# valhalla_v0_3.net
KiCad netlist of a schematic drawn in EAGLE
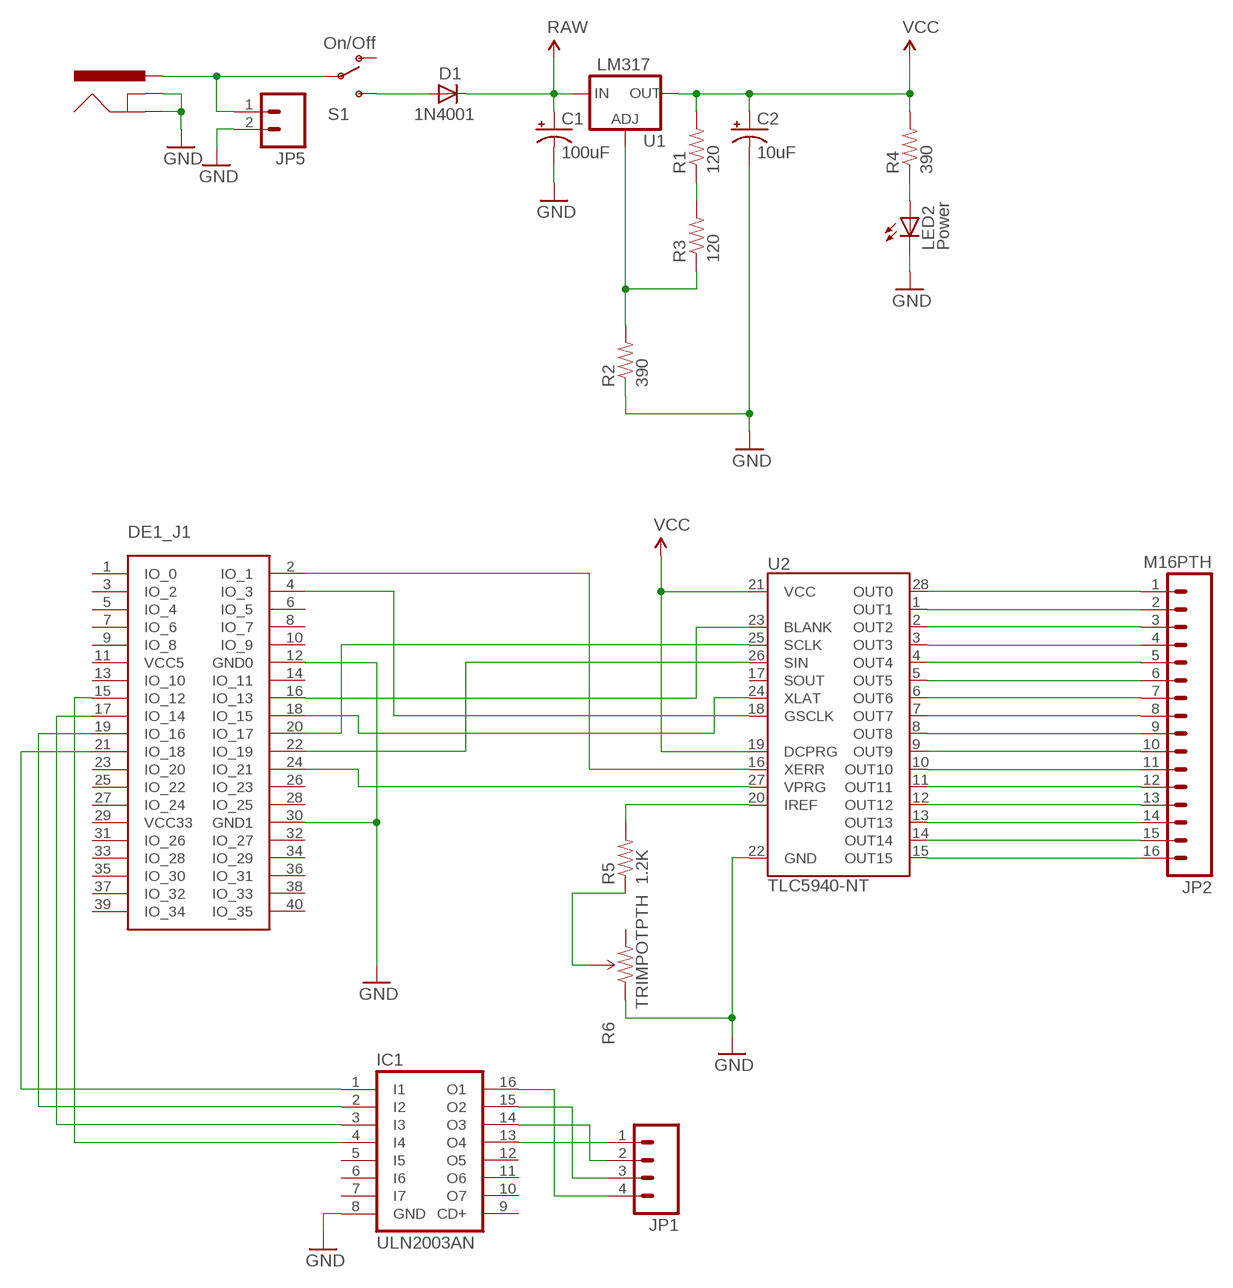
[diagram p0: schematic, sheet 1]

(export (version "E")
  (design (tool "Eeschema 10.0.6"))
  (components
    (comp (ref "C1")
      (value "100uF")
      (footprint "eagle-import:CPOL-RADIAL-100UF-25V")
      (libsource (lib "eagle-import") (part "CAP_POLPTH1"))
    )
    (comp (ref "C2")
      (value "10uF")
      (footprint "eagle-import:CPOL-RADIAL-10UF-25V")
      (libsource (lib "eagle-import") (part "CAP_POLPTH2"))
    )
    (comp (ref "D1")
      (value "1N4001")
      (footprint "eagle-import:DIODE-0.4")
      (libsource (lib "eagle-import") (part "DIODEPTH"))
    )
    (comp (ref "DE1_J1")
      (value "DE1_GPIO_CON40\"")
      (footprint "eagle-import:2X20")
      (libsource (lib "eagle-import") (part "DE1_GPIO_CON40{dblquote}"))
    )
    (comp (ref "IC1")
      (value "ULN2003AN")
      (footprint "eagle-import:DIL16")
      (libsource (lib "eagle-import") (part "ULN2003AN"))
    )
    (comp (ref "J1")
      (value "POWER_JACKPTH")
      (footprint "eagle-import:POWER_JACK_PTH")
      (libsource (lib "eagle-import") (part "POWER_JACKPTH"))
    )
    (comp (ref "JP1")
      (value "M04PTH")
      (footprint "eagle-import:1X04")
      (libsource (lib "eagle-import") (part "M04PTH"))
    )
    (comp (ref "JP2")
      (value "M16PTH")
      (footprint "eagle-import:1X16")
      (libsource (lib "eagle-import") (part "M16PTH"))
    )
    (comp (ref "JP5")
      (value "M02PTH")
      (footprint "eagle-import:1X02")
      (libsource (lib "eagle-import") (part "M02PTH"))
    )
    (comp (ref "LED2")
      (value "Power")
      (footprint "eagle-import:LED5MM")
      (libsource (lib "eagle-import") (part "LED5MM"))
    )
    (comp (ref "R1")
      (value "120")
      (footprint "eagle-import:AXIAL-0.3")
      (libsource (lib "eagle-import") (part "RESISTORPTH1"))
    )
    (comp (ref "R2")
      (value "390")
      (footprint "eagle-import:AXIAL-0.3")
      (libsource (lib "eagle-import") (part "RESISTORPTH1"))
    )
    (comp (ref "R3")
      (value "120")
      (footprint "eagle-import:AXIAL-0.3")
      (libsource (lib "eagle-import") (part "RESISTORPTH1"))
    )
    (comp (ref "R4")
      (value "390")
      (footprint "eagle-import:AXIAL-0.3")
      (libsource (lib "eagle-import") (part "RESISTORPTH1"))
    )
    (comp (ref "R5")
      (value "1.2K")
      (footprint "eagle-import:AXIAL-0.5")
      (libsource (lib "eagle-import") (part "RESISTORPTH-1/2W"))
    )
    (comp (ref "R6")
      (value "TRIMPOTPTH")
      (footprint "eagle-import:TRIM_POT_PTH")
      (libsource (lib "eagle-import") (part "TRIMPOTPTH"))
    )
    (comp (ref "S1")
      (value "On/Off")
      (footprint "eagle-import:SWITCH-SPST")
      (libsource (lib "eagle-import") (part "SWITCH-SPSTPTH"))
    )
    (comp (ref "U1")
      (value "LM317")
      (footprint "eagle-import:TO220-ADJ")
      (libsource (lib "eagle-import") (part "V_REG_317SINK"))
    )
    (comp (ref "U2")
      (value "TLC5940-NT")
      (footprint "eagle-import:DIL28-3")
      (libsource (lib "eagle-import") (part "TLC5940-NT"))
    )
  )
  (nets
    (net (code "1") (name "/VCC5") (class "Default")
      (node (ref "DE1_J1") (pin "11") (pinfunction "VCC5_11") (pintype "power_in"))
    )
    (net (code "2") (name "/VCC33") (class "Default")
      (node (ref "DE1_J1") (pin "29") (pinfunction "VCC33_29") (pintype "power_in"))
    )
    (net (code "3") (name "GND") (class "Default")
      (node (ref "C1") (pin "2") (pinfunction "-_2") (pintype "passive"))
      (node (ref "C2") (pin "2") (pinfunction "-_2") (pintype "passive"))
      (node (ref "DE1_J1") (pin "12") (pinfunction "GND0_12") (pintype "power_in"))
      (node (ref "DE1_J1") (pin "30") (pinfunction "GND1_30") (pintype "power_in"))
      (node (ref "IC1") (pin "8") (pinfunction "GND_8") (pintype "power_in"))
      (node (ref "J1") (pin "GND") (pinfunction "GND_GND") (pintype "bidirectional"))
      (node (ref "J1") (pin "GNDBREAK") (pinfunction "GNDBREAK_GNDBREAK") (pintype "bidirectional"))
      (node (ref "JP5") (pin "2") (pinfunction "2_2") (pintype "passive"))
      (node (ref "LED2") (pin "K") (pinfunction "C_K") (pintype "passive"))
      (node (ref "R2") (pin "P$1") (pinfunction "1_P$1") (pintype "passive"))
      (node (ref "R6") (pin "1") (pinfunction "CCW_1") (pintype "passive"))
      (node (ref "U2") (pin "22") (pinfunction "GND_22") (pintype "bidirectional"))
    )
    (net (code "4") (name "Net-(DE1_J1-IO_1)") (class "Default")
      (node (ref "DE1_J1") (pin "2") (pinfunction "IO_1_2") (pintype "bidirectional"))
      (node (ref "U2") (pin "16") (pinfunction "XERR_16") (pintype "bidirectional"))
    )
    (net (code "5") (name "Net-(DE1_J1-IO_3)") (class "Default")
      (node (ref "DE1_J1") (pin "4") (pinfunction "IO_3_4") (pintype "bidirectional"))
      (node (ref "U2") (pin "18") (pinfunction "GSCLK_18") (pintype "bidirectional"))
    )
    (net (code "6") (name "Net-(DE1_J1-IO_12)") (class "Default")
      (node (ref "DE1_J1") (pin "15") (pinfunction "IO_12_15") (pintype "bidirectional"))
      (node (ref "IC1") (pin "4") (pinfunction "I4_4") (pintype "input"))
    )
    (net (code "7") (name "Net-(DE1_J1-IO_13)") (class "Default")
      (node (ref "DE1_J1") (pin "16") (pinfunction "IO_13_16") (pintype "bidirectional"))
      (node (ref "U2") (pin "23") (pinfunction "BLANK_23") (pintype "bidirectional"))
    )
    (net (code "8") (name "Net-(DE1_J1-IO_14)") (class "Default")
      (node (ref "DE1_J1") (pin "17") (pinfunction "IO_14_17") (pintype "bidirectional"))
      (node (ref "IC1") (pin "3") (pinfunction "I3_3") (pintype "input"))
    )
    (net (code "9") (name "Net-(DE1_J1-IO_15)") (class "Default")
      (node (ref "DE1_J1") (pin "18") (pinfunction "IO_15_18") (pintype "bidirectional"))
      (node (ref "U2") (pin "24") (pinfunction "XLAT_24") (pintype "bidirectional"))
    )
    (net (code "10") (name "Net-(DE1_J1-IO_16)") (class "Default")
      (node (ref "DE1_J1") (pin "19") (pinfunction "IO_16_19") (pintype "bidirectional"))
      (node (ref "IC1") (pin "2") (pinfunction "I2_2") (pintype "input"))
    )
    (net (code "11") (name "Net-(DE1_J1-IO_17)") (class "Default")
      (node (ref "DE1_J1") (pin "20") (pinfunction "IO_17_20") (pintype "bidirectional"))
      (node (ref "U2") (pin "25") (pinfunction "SCLK_25") (pintype "bidirectional"))
    )
    (net (code "12") (name "Net-(DE1_J1-IO_18)") (class "Default")
      (node (ref "DE1_J1") (pin "21") (pinfunction "IO_18_21") (pintype "bidirectional"))
      (node (ref "IC1") (pin "1") (pinfunction "I1_1") (pintype "input"))
    )
    (net (code "13") (name "Net-(DE1_J1-IO_19)") (class "Default")
      (node (ref "DE1_J1") (pin "22") (pinfunction "IO_19_22") (pintype "bidirectional"))
      (node (ref "U2") (pin "26") (pinfunction "SIN_26") (pintype "bidirectional"))
    )
    (net (code "14") (name "Net-(DE1_J1-IO_21)") (class "Default")
      (node (ref "DE1_J1") (pin "24") (pinfunction "IO_21_24") (pintype "bidirectional"))
      (node (ref "U2") (pin "27") (pinfunction "VPRG_27") (pintype "bidirectional"))
    )
    (net (code "15") (name "Net-(IC1-O1)") (class "Default")
      (node (ref "IC1") (pin "16") (pinfunction "O1_16") (pintype "open_collector"))
      (node (ref "JP1") (pin "4") (pinfunction "4_4") (pintype "passive"))
    )
    (net (code "16") (name "Net-(IC1-O2)") (class "Default")
      (node (ref "IC1") (pin "15") (pinfunction "O2_15") (pintype "open_collector"))
      (node (ref "JP1") (pin "3") (pinfunction "3_3") (pintype "passive"))
    )
    (net (code "17") (name "Net-(IC1-O3)") (class "Default")
      (node (ref "IC1") (pin "14") (pinfunction "O3_14") (pintype "open_collector"))
      (node (ref "JP1") (pin "2") (pinfunction "2_2") (pintype "passive"))
    )
    (net (code "18") (name "Net-(IC1-O4)") (class "Default")
      (node (ref "IC1") (pin "13") (pinfunction "O4_13") (pintype "open_collector"))
      (node (ref "JP1") (pin "1") (pinfunction "1_1") (pintype "passive"))
    )
    (net (code "19") (name "Net-(R1-1)") (class "Default")
      (node (ref "R1") (pin "P$1") (pinfunction "1_P$1") (pintype "passive"))
      (node (ref "R3") (pin "P$2") (pinfunction "2_P$2") (pintype "passive"))
    )
    (net (code "20") (name "Net-(R2-2)") (class "Default")
      (node (ref "R2") (pin "P$2") (pinfunction "2_P$2") (pintype "passive"))
      (node (ref "R3") (pin "P$1") (pinfunction "1_P$1") (pintype "passive"))
      (node (ref "U1") (pin "ADJ") (pinfunction "ADJ_ADJ") (pintype "input"))
    )
    (net (code "21") (name "Net-(R4-1)") (class "Default")
      (node (ref "LED2") (pin "A") (pinfunction "A_A") (pintype "passive"))
      (node (ref "R4") (pin "P$1") (pinfunction "1_P$1") (pintype "passive"))
    )
    (net (code "22") (name "Net-(R5-1)") (class "Default")
      (node (ref "R5") (pin "P$1") (pinfunction "1_P$1") (pintype "passive"))
      (node (ref "R6") (pin "2") (pinfunction "WIPER_2") (pintype "passive"))
    )
    (net (code "23") (name "Net-(R5-2)") (class "Default")
      (node (ref "R5") (pin "P$2") (pinfunction "2_P$2") (pintype "passive"))
      (node (ref "U2") (pin "20") (pinfunction "IREF_20") (pintype "bidirectional"))
    )
    (net (code "24") (name "Net-(S1-P)") (class "Default")
      (node (ref "J1") (pin "PWR") (pinfunction "PWR_PWR") (pintype "bidirectional"))
      (node (ref "JP5") (pin "1") (pinfunction "1_1") (pintype "passive"))
      (node (ref "S1") (pin "2") (pinfunction "P_2") (pintype "passive"))
    )
    (net (code "25") (name "Net-(S1-S)") (class "Default")
      (node (ref "D1") (pin "A") (pinfunction "A_A") (pintype "passive"))
      (node (ref "S1") (pin "3") (pinfunction "S_3") (pintype "passive"))
    )
    (net (code "26") (name "Net-(U2-OUT0)") (class "Default")
      (node (ref "JP2") (pin "1") (pinfunction "1_1") (pintype "passive"))
      (node (ref "U2") (pin "28") (pinfunction "OUT0_28") (pintype "bidirectional"))
    )
    (net (code "27") (name "Net-(U2-OUT1)") (class "Default")
      (node (ref "JP2") (pin "2") (pinfunction "2_2") (pintype "passive"))
      (node (ref "U2") (pin "1") (pinfunction "OUT1_1") (pintype "bidirectional"))
    )
    (net (code "28") (name "Net-(U2-OUT2)") (class "Default")
      (node (ref "JP2") (pin "3") (pinfunction "3_3") (pintype "passive"))
      (node (ref "U2") (pin "2") (pinfunction "OUT2_2") (pintype "bidirectional"))
    )
    (net (code "29") (name "Net-(U2-OUT3)") (class "Default")
      (node (ref "JP2") (pin "4") (pinfunction "4_4") (pintype "passive"))
      (node (ref "U2") (pin "3") (pinfunction "OUT3_3") (pintype "bidirectional"))
    )
    (net (code "30") (name "Net-(U2-OUT4)") (class "Default")
      (node (ref "JP2") (pin "5") (pinfunction "5_5") (pintype "passive"))
      (node (ref "U2") (pin "4") (pinfunction "OUT4_4") (pintype "bidirectional"))
    )
    (net (code "31") (name "Net-(U2-OUT5)") (class "Default")
      (node (ref "JP2") (pin "6") (pinfunction "6_6") (pintype "passive"))
      (node (ref "U2") (pin "5") (pinfunction "OUT5_5") (pintype "bidirectional"))
    )
    (net (code "32") (name "Net-(U2-OUT6)") (class "Default")
      (node (ref "JP2") (pin "7") (pinfunction "7_7") (pintype "passive"))
      (node (ref "U2") (pin "6") (pinfunction "OUT6_6") (pintype "bidirectional"))
    )
    (net (code "33") (name "Net-(U2-OUT7)") (class "Default")
      (node (ref "JP2") (pin "8") (pinfunction "8_8") (pintype "passive"))
      (node (ref "U2") (pin "7") (pinfunction "OUT7_7") (pintype "bidirectional"))
    )
    (net (code "34") (name "Net-(U2-OUT8)") (class "Default")
      (node (ref "JP2") (pin "9") (pinfunction "9_9") (pintype "passive"))
      (node (ref "U2") (pin "8") (pinfunction "OUT8_8") (pintype "bidirectional"))
    )
    (net (code "35") (name "Net-(U2-OUT9)") (class "Default")
      (node (ref "JP2") (pin "10") (pinfunction "10_10") (pintype "passive"))
      (node (ref "U2") (pin "9") (pinfunction "OUT9_9") (pintype "bidirectional"))
    )
    (net (code "36") (name "Net-(U2-OUT10)") (class "Default")
      (node (ref "JP2") (pin "11") (pinfunction "11_11") (pintype "passive"))
      (node (ref "U2") (pin "10") (pinfunction "OUT10_10") (pintype "bidirectional"))
    )
    (net (code "37") (name "Net-(U2-OUT11)") (class "Default")
      (node (ref "JP2") (pin "12") (pinfunction "12_12") (pintype "passive"))
      (node (ref "U2") (pin "11") (pinfunction "OUT11_11") (pintype "bidirectional"))
    )
    (net (code "38") (name "Net-(U2-OUT12)") (class "Default")
      (node (ref "JP2") (pin "13") (pinfunction "13_13") (pintype "passive"))
      (node (ref "U2") (pin "12") (pinfunction "OUT12_12") (pintype "bidirectional"))
    )
    (net (code "39") (name "Net-(U2-OUT13)") (class "Default")
      (node (ref "JP2") (pin "14") (pinfunction "14_14") (pintype "passive"))
      (node (ref "U2") (pin "13") (pinfunction "OUT13_13") (pintype "bidirectional"))
    )
    (net (code "40") (name "Net-(U2-OUT14)") (class "Default")
      (node (ref "JP2") (pin "15") (pinfunction "15_15") (pintype "passive"))
      (node (ref "U2") (pin "14") (pinfunction "OUT14_14") (pintype "bidirectional"))
    )
    (net (code "41") (name "Net-(U2-OUT15)") (class "Default")
      (node (ref "JP2") (pin "16") (pinfunction "16_16") (pintype "passive"))
      (node (ref "U2") (pin "15") (pinfunction "OUT15_15") (pintype "bidirectional"))
    )
    (net (code "42") (name "RAW") (class "Default")
      (node (ref "C1") (pin "1") (pinfunction "+_1") (pintype "passive"))
      (node (ref "D1") (pin "C") (pinfunction "C_C") (pintype "passive"))
      (node (ref "U1") (pin "IN") (pinfunction "IN_IN") (pintype "input"))
    )
    (net (code "43") (name "VCC") (class "Default")
      (node (ref "C2") (pin "1") (pinfunction "+_1") (pintype "passive"))
      (node (ref "R1") (pin "P$2") (pinfunction "2_P$2") (pintype "passive"))
      (node (ref "R4") (pin "P$2") (pinfunction "2_P$2") (pintype "passive"))
      (node (ref "U1") (pin "OUT") (pinfunction "OUT_OUT") (pintype "output"))
      (node (ref "U2") (pin "19") (pinfunction "DCPRG_19") (pintype "bidirectional"))
      (node (ref "U2") (pin "21") (pinfunction "VCC_21") (pintype "bidirectional"))
    )
    (net (code "44") (name "unconnected-(DE1_J1-IO_0-Pad1)") (class "Default")
      (node (ref "DE1_J1") (pin "1") (pinfunction "IO_0_1") (pintype "bidirectional"))
    )
    (net (code "45") (name "unconnected-(DE1_J1-IO_2-Pad3)") (class "Default")
      (node (ref "DE1_J1") (pin "3") (pinfunction "IO_2_3") (pintype "bidirectional"))
    )
    (net (code "46") (name "unconnected-(DE1_J1-IO_4-Pad5)") (class "Default")
      (node (ref "DE1_J1") (pin "5") (pinfunction "IO_4_5") (pintype "bidirectional"))
    )
    (net (code "47") (name "unconnected-(DE1_J1-IO_5-Pad6)") (class "Default")
      (node (ref "DE1_J1") (pin "6") (pinfunction "IO_5_6") (pintype "bidirectional"))
    )
    (net (code "48") (name "unconnected-(DE1_J1-IO_6-Pad7)") (class "Default")
      (node (ref "DE1_J1") (pin "7") (pinfunction "IO_6_7") (pintype "bidirectional"))
    )
    (net (code "49") (name "unconnected-(DE1_J1-IO_7-Pad8)") (class "Default")
      (node (ref "DE1_J1") (pin "8") (pinfunction "IO_7_8") (pintype "bidirectional"))
    )
    (net (code "50") (name "unconnected-(DE1_J1-IO_8-Pad9)") (class "Default")
      (node (ref "DE1_J1") (pin "9") (pinfunction "IO_8_9") (pintype "bidirectional"))
    )
    (net (code "51") (name "unconnected-(DE1_J1-IO_9-Pad10)") (class "Default")
      (node (ref "DE1_J1") (pin "10") (pinfunction "IO_9_10") (pintype "bidirectional"))
    )
    (net (code "52") (name "unconnected-(DE1_J1-IO_10-Pad13)") (class "Default")
      (node (ref "DE1_J1") (pin "13") (pinfunction "IO_10_13") (pintype "bidirectional"))
    )
    (net (code "53") (name "unconnected-(DE1_J1-IO_11-Pad14)") (class "Default")
      (node (ref "DE1_J1") (pin "14") (pinfunction "IO_11_14") (pintype "bidirectional"))
    )
    (net (code "54") (name "unconnected-(DE1_J1-IO_20-Pad23)") (class "Default")
      (node (ref "DE1_J1") (pin "23") (pinfunction "IO_20_23") (pintype "bidirectional"))
    )
    (net (code "55") (name "unconnected-(DE1_J1-IO_22-Pad25)") (class "Default")
      (node (ref "DE1_J1") (pin "25") (pinfunction "IO_22_25") (pintype "bidirectional"))
    )
    (net (code "56") (name "unconnected-(DE1_J1-IO_23-Pad26)") (class "Default")
      (node (ref "DE1_J1") (pin "26") (pinfunction "IO_23_26") (pintype "bidirectional"))
    )
    (net (code "57") (name "unconnected-(DE1_J1-IO_24-Pad27)") (class "Default")
      (node (ref "DE1_J1") (pin "27") (pinfunction "IO_24_27") (pintype "bidirectional"))
    )
    (net (code "58") (name "unconnected-(DE1_J1-IO_25-Pad28)") (class "Default")
      (node (ref "DE1_J1") (pin "28") (pinfunction "IO_25_28") (pintype "bidirectional"))
    )
    (net (code "59") (name "unconnected-(DE1_J1-IO_26-Pad31)") (class "Default")
      (node (ref "DE1_J1") (pin "31") (pinfunction "IO_26_31") (pintype "bidirectional"))
    )
    (net (code "60") (name "unconnected-(DE1_J1-IO_27-Pad32)") (class "Default")
      (node (ref "DE1_J1") (pin "32") (pinfunction "IO_27_32") (pintype "bidirectional"))
    )
    (net (code "61") (name "unconnected-(DE1_J1-IO_28-Pad33)") (class "Default")
      (node (ref "DE1_J1") (pin "33") (pinfunction "IO_28_33") (pintype "bidirectional"))
    )
    (net (code "62") (name "unconnected-(DE1_J1-IO_29-Pad34)") (class "Default")
      (node (ref "DE1_J1") (pin "34") (pinfunction "IO_29_34") (pintype "bidirectional"))
    )
    (net (code "63") (name "unconnected-(DE1_J1-IO_30-Pad35)") (class "Default")
      (node (ref "DE1_J1") (pin "35") (pinfunction "IO_30_35") (pintype "bidirectional"))
    )
    (net (code "64") (name "unconnected-(DE1_J1-IO_31-Pad36)") (class "Default")
      (node (ref "DE1_J1") (pin "36") (pinfunction "IO_31_36") (pintype "bidirectional"))
    )
    (net (code "65") (name "unconnected-(DE1_J1-IO_32-Pad37)") (class "Default")
      (node (ref "DE1_J1") (pin "37") (pinfunction "IO_32_37") (pintype "bidirectional"))
    )
    (net (code "66") (name "unconnected-(DE1_J1-IO_33-Pad38)") (class "Default")
      (node (ref "DE1_J1") (pin "38") (pinfunction "IO_33_38") (pintype "bidirectional"))
    )
    (net (code "67") (name "unconnected-(DE1_J1-IO_34-Pad39)") (class "Default")
      (node (ref "DE1_J1") (pin "39") (pinfunction "IO_34_39") (pintype "bidirectional"))
    )
    (net (code "68") (name "unconnected-(DE1_J1-IO_35-Pad40)") (class "Default")
      (node (ref "DE1_J1") (pin "40") (pinfunction "IO_35_40") (pintype "bidirectional"))
    )
    (net (code "69") (name "unconnected-(IC1-CD+-Pad9)") (class "Default")
      (node (ref "IC1") (pin "9") (pinfunction "CD+_9") (pintype "passive"))
    )
    (net (code "70") (name "unconnected-(IC1-I5-Pad5)") (class "Default")
      (node (ref "IC1") (pin "5") (pinfunction "I5_5") (pintype "input"))
    )
    (net (code "71") (name "unconnected-(IC1-I6-Pad6)") (class "Default")
      (node (ref "IC1") (pin "6") (pinfunction "I6_6") (pintype "input"))
    )
    (net (code "72") (name "unconnected-(IC1-I7-Pad7)") (class "Default")
      (node (ref "IC1") (pin "7") (pinfunction "I7_7") (pintype "input"))
    )
    (net (code "73") (name "unconnected-(IC1-O5-Pad12)") (class "Default")
      (node (ref "IC1") (pin "12") (pinfunction "O5_12") (pintype "open_collector"))
    )
    (net (code "74") (name "unconnected-(IC1-O6-Pad11)") (class "Default")
      (node (ref "IC1") (pin "11") (pinfunction "O6_11") (pintype "open_collector"))
    )
    (net (code "75") (name "unconnected-(IC1-O7-Pad10)") (class "Default")
      (node (ref "IC1") (pin "10") (pinfunction "O7_10") (pintype "open_collector"))
    )
    (net (code "76") (name "unconnected-(R6-CW-Pad3)") (class "Default")
      (node (ref "R6") (pin "3") (pinfunction "CW_3") (pintype "passive"))
    )
    (net (code "77") (name "unconnected-(S1-O-Pad1)") (class "Default")
      (node (ref "S1") (pin "1") (pinfunction "O_1") (pintype "passive"))
    )
    (net (code "78") (name "unconnected-(U2-SOUT-Pad17)") (class "Default")
      (node (ref "U2") (pin "17") (pinfunction "SOUT_17") (pintype "bidirectional"))
    )
  )
)
